# ATtiny20_Study_-_WLCSP12.net
KiCad netlist of a schematic drawn in EAGLE
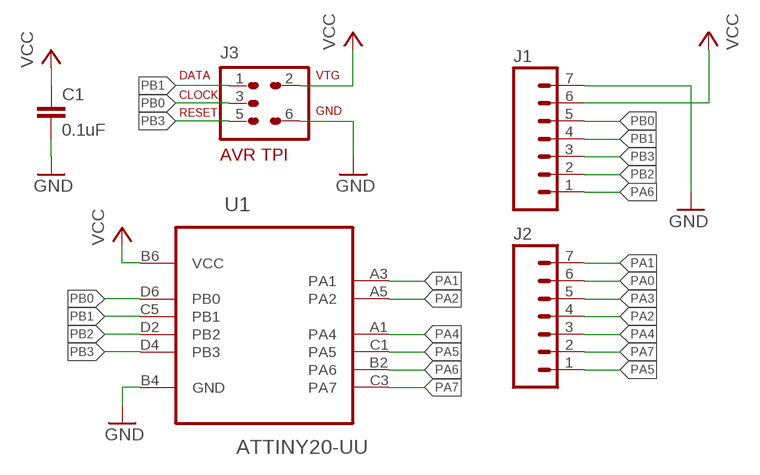
[diagram p0: schematic, sheet 1]

(export (version "E")
  (design (tool "Eeschema 10.0.6"))
  (components
    (comp (ref "C1")
      (value "0.1uF")
      (footprint "eagle-import:0402-CAP")
      (libsource (lib "eagle-import") (part "CAP0402-CAP"))
    )
    (comp (ref "J1")
      (value "M07")
      (footprint "eagle-import:1X07")
      (libsource (lib "eagle-import") (part "M07"))
    )
    (comp (ref "J2")
      (value "M07")
      (footprint "eagle-import:1X07")
      (libsource (lib "eagle-import") (part "M07"))
    )
    (comp (ref "J3")
      (value "AVR-TPIVERT")
      (footprint "eagle-import:AVR-ISP-6")
      (libsource (lib "eagle-import") (part "AVR-TPIVERT"))
    )
    (comp (ref "U1")
      (value "ATTINY20-UU")
      (footprint "eagle-import:12U-1")
      (libsource (lib "eagle-import") (part "ATTINY20-UU"))
    )
  )
  (nets
    (net (code "1") (name "GND") (class "Default")
      (node (ref "C1") (pin "2") (pinfunction "2_2") (pintype "passive"))
      (node (ref "J1") (pin "7") (pinfunction "7_7") (pintype "passive"))
      (node (ref "J3") (pin "6") (pinfunction "6_6") (pintype "passive"))
      (node (ref "U1") (pin "B4") (pinfunction "GND_B4") (pintype "passive"))
    )
    (net (code "2") (name "PA0") (class "Default")
      (node (ref "J2") (pin "6") (pinfunction "6_6") (pintype "passive"))
    )
    (net (code "3") (name "PA1") (class "Default")
      (node (ref "J2") (pin "7") (pinfunction "7_7") (pintype "passive"))
      (node (ref "U1") (pin "A3") (pinfunction "PA1_A3") (pintype "bidirectional"))
    )
    (net (code "4") (name "PA2") (class "Default")
      (node (ref "J2") (pin "4") (pinfunction "4_4") (pintype "passive"))
      (node (ref "U1") (pin "A5") (pinfunction "PA2_A5") (pintype "bidirectional"))
    )
    (net (code "5") (name "PA3") (class "Default")
      (node (ref "J2") (pin "5") (pinfunction "5_5") (pintype "passive"))
    )
    (net (code "6") (name "PA4") (class "Default")
      (node (ref "J2") (pin "3") (pinfunction "3_3") (pintype "passive"))
      (node (ref "U1") (pin "A1") (pinfunction "PA4_A1") (pintype "bidirectional"))
    )
    (net (code "7") (name "PA5") (class "Default")
      (node (ref "J2") (pin "1") (pinfunction "1_1") (pintype "passive"))
      (node (ref "U1") (pin "C1") (pinfunction "PA5_C1") (pintype "bidirectional"))
    )
    (net (code "8") (name "PA6") (class "Default")
      (node (ref "J1") (pin "1") (pinfunction "1_1") (pintype "passive"))
      (node (ref "U1") (pin "B2") (pinfunction "PA6_B2") (pintype "bidirectional"))
    )
    (net (code "9") (name "PA7") (class "Default")
      (node (ref "J2") (pin "2") (pinfunction "2_2") (pintype "passive"))
      (node (ref "U1") (pin "C3") (pinfunction "PA7_C3") (pintype "bidirectional"))
    )
    (net (code "10") (name "PB0") (class "Default")
      (node (ref "J1") (pin "5") (pinfunction "5_5") (pintype "passive"))
      (node (ref "J3") (pin "3") (pinfunction "3_3") (pintype "passive"))
      (node (ref "U1") (pin "D6") (pinfunction "PB0_D6") (pintype "bidirectional"))
    )
    (net (code "11") (name "PB1") (class "Default")
      (node (ref "J1") (pin "4") (pinfunction "4_4") (pintype "passive"))
      (node (ref "J3") (pin "1") (pinfunction "1_1") (pintype "passive"))
      (node (ref "U1") (pin "C5") (pinfunction "PB1_C5") (pintype "bidirectional"))
    )
    (net (code "12") (name "PB2") (class "Default")
      (node (ref "J1") (pin "2") (pinfunction "2_2") (pintype "passive"))
      (node (ref "U1") (pin "D2") (pinfunction "PB2_D2") (pintype "bidirectional"))
    )
    (net (code "13") (name "PB3") (class "Default")
      (node (ref "J1") (pin "3") (pinfunction "3_3") (pintype "passive"))
      (node (ref "J3") (pin "5") (pinfunction "5_5") (pintype "passive"))
      (node (ref "U1") (pin "D4") (pinfunction "PB3_D4") (pintype "bidirectional"))
    )
    (net (code "14") (name "VCC") (class "Default")
      (node (ref "C1") (pin "1") (pinfunction "1_1") (pintype "passive"))
      (node (ref "J1") (pin "6") (pinfunction "6_6") (pintype "passive"))
      (node (ref "J3") (pin "2") (pinfunction "2_2") (pintype "passive"))
      (node (ref "U1") (pin "B6") (pinfunction "VCC_B6") (pintype "power_in"))
    )
  )
)
